# EPS_MPPT_Y_OR_Solar.net
KiCad netlist of a schematic drawn in Altium Designer
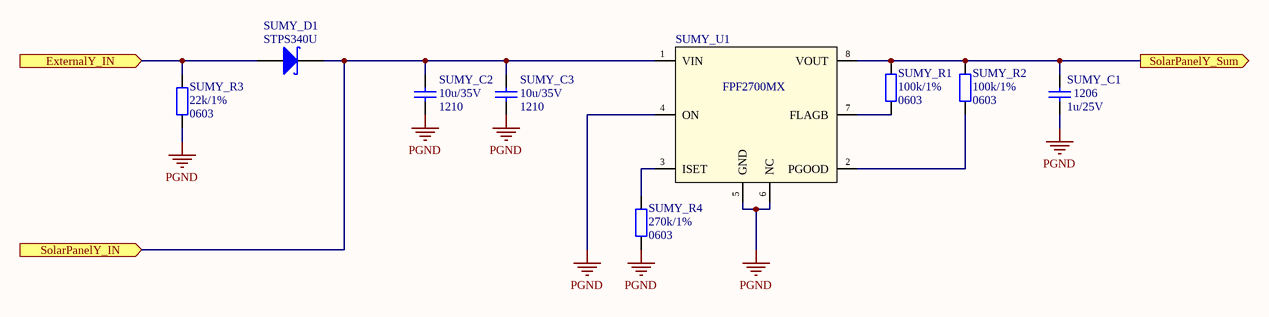
[diagram p0: EPS_MPPT_Y_OR_Solar.SchDoc]

(export (version "E")
  (design (tool "Eeschema 10.0.6"))
  (components
    (comp (ref "SUMY_C1")
      (value "1u/25V")
      (footprint "SMD_Capacitor_1206")
      (description "Ceramic Cap Kemet COTS 1u/25V X7R 1206")
      (fields
        (field (name "MANUFACTURERPARTNUMBER") "C1206T105K3RALTU")
        (field (name "MANUFACTURER") "Kemet")
        (field (name "PACKAGE") "1206")
      )
      (libsource (lib "capacitors") (part "Cer_C1206T105K3RALTU"))
    )
    (comp (ref "SUMY_C2")
      (value "10u/35V")
      (footprint "SMD_Capacitor_1210")
      (description "Ceramic Cap Murata Automotive 10u/35V X7S 1210")
      (fields
        (field (name "MANUFACTURER") "Murata")
        (field (name "MANUFACTURERPARTNUMBER") "GCM32EC7YA106KA03K")
        (field (name "PACKAGE") "1210")
      )
      (libsource (lib "capacitors") (part "Cer_GCM32EC7YA106KA03K"))
    )
    (comp (ref "SUMY_C3")
      (value "10u/35V")
      (footprint "SMD_Capacitor_1210")
      (description "Ceramic Cap Murata Automotive 10u/35V X7S 1210")
      (fields
        (field (name "MANUFACTURER") "Murata")
        (field (name "MANUFACTURERPARTNUMBER") "GCM32EC7YA106KA03K")
        (field (name "PACKAGE") "1210")
      )
      (libsource (lib "capacitors") (part "Cer_GCM32EC7YA106KA03K"))
    )
    (comp (ref "SUMY_D1")
      (value "STPS340U")
      (footprint "DO-214AA")
      (description "3A/40V Power Schottky Rectifier.")
      (fields (field (name "MANUFACTURER") "STMicroelectronics"))
      (libsource (lib "diodes") (part "STPS340x"))
    )
    (comp (ref "SUMY_R1")
      (value "100k/1%")
      (footprint "SMD_Resistor_0603")
      (fields (field (name "PACKAGE") "0603"))
      (libsource (lib "resistors") (part "Res"))
    )
    (comp (ref "SUMY_R2")
      (value "100k/1%")
      (footprint "SMD_Resistor_0603")
      (fields (field (name "PACKAGE") "0603"))
      (libsource (lib "resistors") (part "Res"))
    )
    (comp (ref "SUMY_R3")
      (value "22k/1%")
      (footprint "SMD_Resistor_0603")
      (fields (field (name "PACKAGE") "0603"))
      (libsource (lib "resistors") (part "Res"))
    )
    (comp (ref "SUMY_R4")
      (value "270k/1%")
      (footprint "SMD_Resistor_0603")
      (fields (field (name "PACKAGE") "0603"))
      (libsource (lib "resistors") (part "Res"))
    )
    (comp (ref "SUMY_U1")
      (value "FPF2700MX")
      (footprint "SOIC-8-N")
      (description "Adj over-current protection 0.4-2A, Load Switch")
      (fields (field (name "MANUFACTURER") "Fairchild Semiconductor"))
      (libsource (lib "microcircuits") (part "FPF2700MX"))
    )
  )
  (nets
    (net (code "1") (name "/ExternalY_IN") (class "Default")
      (node (ref "SUMY_D1") (pin "A") (pinfunction "A_A") (pintype "passive"))
      (node (ref "SUMY_R3") (pin "1") (pinfunction "1_1") (pintype "passive"))
    )
    (net (code "2") (name "/SolarPanelY_IN") (class "Default")
      (node (ref "SUMY_C2") (pin "1") (pinfunction "1_1") (pintype "passive"))
      (node (ref "SUMY_C3") (pin "1") (pinfunction "1_1") (pintype "passive"))
      (node (ref "SUMY_D1") (pin "K") (pinfunction "K_K") (pintype "passive"))
      (node (ref "SUMY_U1") (pin "1") (pinfunction "VIN_1") (pintype "passive"))
    )
    (net (code "3") (name "/SolarPanelY_Sum") (class "Default")
      (node (ref "SUMY_C1") (pin "1") (pinfunction "1_1") (pintype "passive"))
      (node (ref "SUMY_R1") (pin "1") (pinfunction "1_1") (pintype "passive"))
      (node (ref "SUMY_R2") (pin "1") (pinfunction "1_1") (pintype "passive"))
      (node (ref "SUMY_U1") (pin "8") (pinfunction "VOUT_8") (pintype "passive"))
    )
    (net (code "4") (name "Net-(SUMY_U1-FLAGB)") (class "Default")
      (node (ref "SUMY_R1") (pin "2") (pinfunction "2_2") (pintype "passive"))
      (node (ref "SUMY_U1") (pin "7") (pinfunction "FLAGB_7") (pintype "passive"))
    )
    (net (code "5") (name "Net-(SUMY_U1-ISET)") (class "Default")
      (node (ref "SUMY_R4") (pin "1") (pinfunction "1_1") (pintype "passive"))
      (node (ref "SUMY_U1") (pin "3") (pinfunction "ISET_3") (pintype "passive"))
    )
    (net (code "6") (name "Net-(SUMY_U1-PGOOD)") (class "Default")
      (node (ref "SUMY_R2") (pin "2") (pinfunction "2_2") (pintype "passive"))
      (node (ref "SUMY_U1") (pin "2") (pinfunction "PGOOD_2") (pintype "passive"))
    )
    (net (code "7") (name "PGND") (class "Default")
      (node (ref "SUMY_C1") (pin "2") (pinfunction "2_2") (pintype "passive"))
      (node (ref "SUMY_C2") (pin "2") (pinfunction "2_2") (pintype "passive"))
      (node (ref "SUMY_C3") (pin "2") (pinfunction "2_2") (pintype "passive"))
      (node (ref "SUMY_R3") (pin "2") (pinfunction "2_2") (pintype "passive"))
      (node (ref "SUMY_R4") (pin "2") (pinfunction "2_2") (pintype "passive"))
      (node (ref "SUMY_U1") (pin "4") (pinfunction "ON_4") (pintype "passive"))
      (node (ref "SUMY_U1") (pin "5") (pinfunction "GND_5") (pintype "passive"))
      (node (ref "SUMY_U1") (pin "6") (pinfunction "NC_6") (pintype "passive"))
    )
  )
)
